# HDMI.net
KiCad netlist of a schematic drawn in Altium Designer
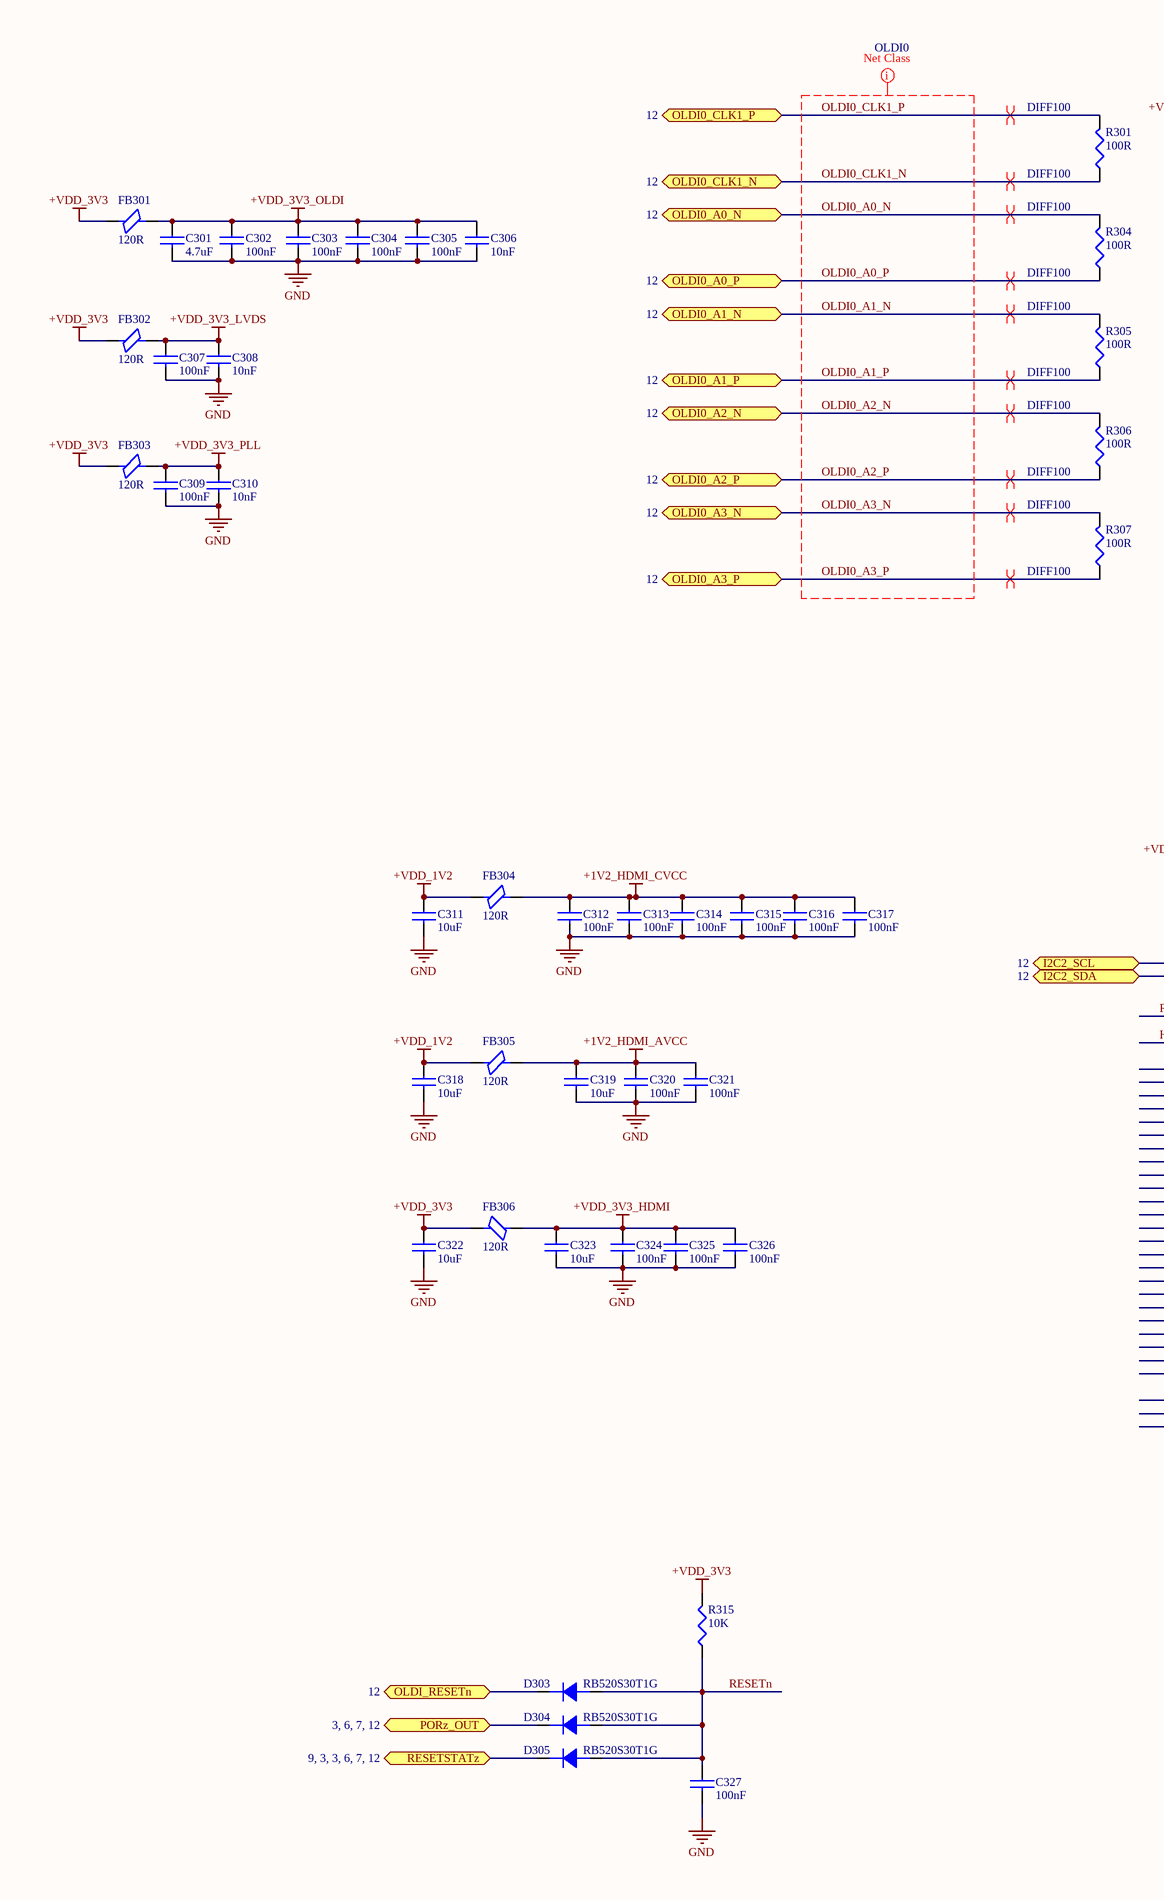
[diagram p0: HDMI.SchDoc, left]
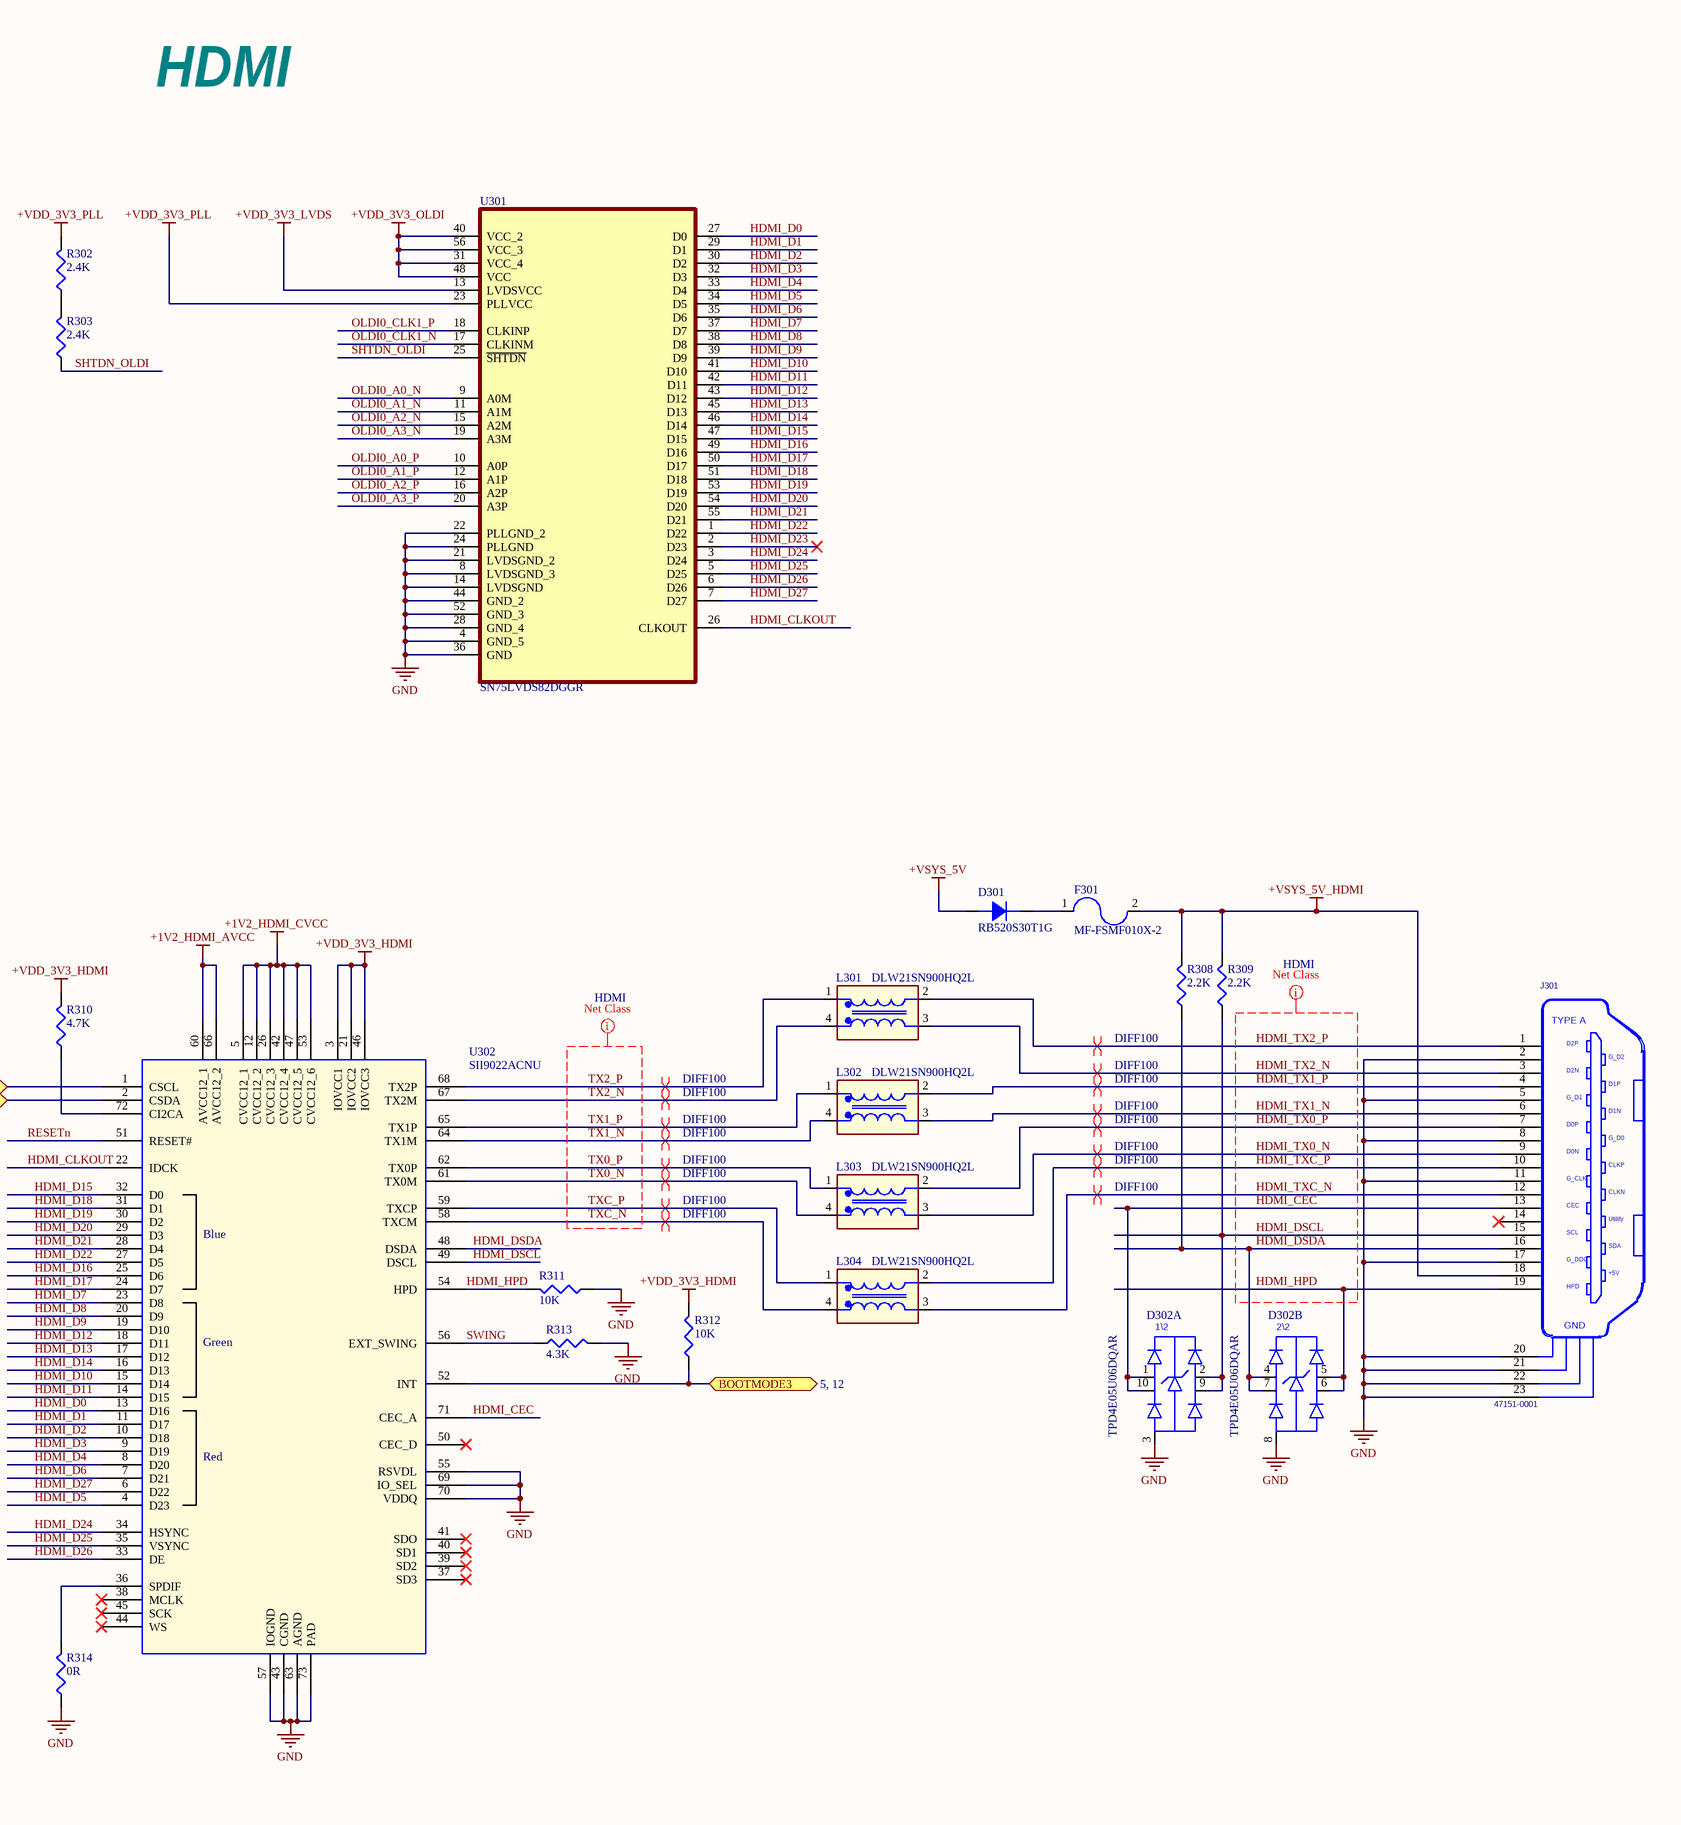
[diagram p1: HDMI.SchDoc, right]

(export (version "E")
  (design (tool "Eeschema 10.0.6"))
  (components
    (comp (ref "C301")
      (value "4.7uF")
      (footprint "C0402")
      (description "Multilayer Ceramic Capacitor, 4.7 uF, 6.3V, ± 10%, X5R, 0402 [1005 Metric]")
      (fields
        (field (name "MANUFACTURER") "Yageo")
        (field (name "MANUFACTURER PART NUMBER") "CC0402MRX5R5BB475")
      )
      (libsource (lib "Schlib SOM AM625") (part "CC0402MRX5R5BB475"))
    )
    (comp (ref "C302")
      (value "100nF")
      (footprint "C0603")
      (description "Multilayer Ceramic Capacitor, 0.1 uF, 25 V, ± 10%, X7R, 0603 [1608 Metric]")
      (fields
        (field (name "MANUFACTURER") "TDK")
        (field (name "MANUFACTURER PART NUMBER") "C1608X7R1E104K080AA")
      )
      (libsource (lib "Schlib SOM AM625") (part "C1608X7R1E104K080AA"))
    )
    (comp (ref "C303")
      (value "100nF")
      (footprint "C0603")
      (description "Multilayer Ceramic Capacitor, 0.1 uF, 25 V, ± 10%, X7R, 0603 [1608 Metric]")
      (fields
        (field (name "MANUFACTURER") "TDK")
        (field (name "MANUFACTURER PART NUMBER") "C1608X7R1E104K080AA")
      )
      (libsource (lib "Schlib SOM AM625") (part "C1608X7R1E104K080AA"))
    )
    (comp (ref "C304")
      (value "100nF")
      (footprint "C0603")
      (description "Multilayer Ceramic Capacitor, 0.1 uF, 25 V, ± 10%, X7R, 0603 [1608 Metric]")
      (fields
        (field (name "MANUFACTURER") "TDK")
        (field (name "MANUFACTURER PART NUMBER") "C1608X7R1E104K080AA")
      )
      (libsource (lib "Schlib SOM AM625") (part "C1608X7R1E104K080AA"))
    )
    (comp (ref "C305")
      (value "100nF")
      (footprint "C0603")
      (description "Multilayer Ceramic Capacitor, 0.1 uF, 25 V, ± 10%, X7R, 0603 [1608 Metric]")
      (fields
        (field (name "MANUFACTURER") "TDK")
        (field (name "MANUFACTURER PART NUMBER") "C1608X7R1E104K080AA")
      )
      (libsource (lib "Schlib SOM AM625") (part "C1608X7R1E104K080AA"))
    )
    (comp (ref "C306")
      (value "10nF")
      (footprint "C0402")
      (description "ESD SMD Comm X7R 0402 (1005Metric) ceramic capacitor 0.039Lx0.020W 1.00mmx0.50mm X7R ±10% 10000pF")
      (fields
        (field (name "MANUFACTURER") "KEMET")
        (field (name "MANUFACTURER PART NUMBER") "C0402C103K4REC7411")
      )
      (libsource (lib "Schlib SOM AM625") (part "C0402C103K4REC7411"))
    )
    (comp (ref "C307")
      (value "100nF")
      (footprint "C0603")
      (description "Multilayer Ceramic Capacitor, 0.1 uF, 25 V, ± 10%, X7R, 0603 [1608 Metric]")
      (fields
        (field (name "MANUFACTURER") "TDK")
        (field (name "MANUFACTURER PART NUMBER") "C1608X7R1E104K080AA")
      )
      (libsource (lib "Schlib SOM AM625") (part "C1608X7R1E104K080AA"))
    )
    (comp (ref "C308")
      (value "10nF")
      (footprint "C0402")
      (description "ESD SMD Comm X7R 0402 (1005Metric) ceramic capacitor 0.039Lx0.020W 1.00mmx0.50mm X7R ±10% 10000pF")
      (fields
        (field (name "MANUFACTURER") "KEMET")
        (field (name "MANUFACTURER PART NUMBER") "C0402C103K4REC7411")
      )
      (libsource (lib "Schlib SOM AM625") (part "C0402C103K4REC7411"))
    )
    (comp (ref "C309")
      (value "100nF")
      (footprint "C0603")
      (description "Multilayer Ceramic Capacitor, 0.1 uF, 25 V, ± 10%, X7R, 0603 [1608 Metric]")
      (fields
        (field (name "MANUFACTURER") "TDK")
        (field (name "MANUFACTURER PART NUMBER") "C1608X7R1E104K080AA")
      )
      (libsource (lib "Schlib SOM AM625") (part "C1608X7R1E104K080AA"))
    )
    (comp (ref "C310")
      (value "10nF")
      (footprint "C0402")
      (description "ESD SMD Comm X7R 0402 (1005Metric) ceramic capacitor 0.039Lx0.020W 1.00mmx0.50mm X7R ±10% 10000pF")
      (fields
        (field (name "MANUFACTURER") "KEMET")
        (field (name "MANUFACTURER PART NUMBER") "C0402C103K4REC7411")
      )
      (libsource (lib "Schlib SOM AM625") (part "C0402C103K4REC7411"))
    )
    (comp (ref "C311")
      (value "10uF")
      (footprint "C0603")
      (description "Multilayer Ceramic Capacitor, 10 uF, 10 V, ± 10%, X5R, 0603 [1608 Metric]")
      (fields
        (field (name "MANUFACTURER") "TDK")
        (field (name "MANUFACTURER PART NUMBER") "C1608X5R1A106K080AC")
      )
      (libsource (lib "Schlib SOM AM625") (part "C1608X5R1A106K080AC"))
    )
    (comp (ref "C312")
      (value "100nF")
      (footprint "C0201")
      (description "Multilayer Ceramic Capacitor, 0.1 uF, 16 V, ± 10%, X5R, 0201 [0603 Metric]")
      (fields
        (field (name "MANUFACTURER") "Yageo")
        (field (name "MANUFACTURER PART NUMBER") "CC0201KRX5R6BB104")
      )
      (libsource (lib "Schlib SOM AM625") (part "CC0201KRX5R6BB104"))
    )
    (comp (ref "C313")
      (value "100nF")
      (footprint "C0201")
      (description "Multilayer Ceramic Capacitor, 0.1 uF, 16 V, ± 10%, X5R, 0201 [0603 Metric]")
      (fields
        (field (name "MANUFACTURER") "Yageo")
        (field (name "MANUFACTURER PART NUMBER") "CC0201KRX5R6BB104")
      )
      (libsource (lib "Schlib SOM AM625") (part "CC0201KRX5R6BB104"))
    )
    (comp (ref "C314")
      (value "100nF")
      (footprint "C0201")
      (description "Multilayer Ceramic Capacitor, 0.1 uF, 16 V, ± 10%, X5R, 0201 [0603 Metric]")
      (fields
        (field (name "MANUFACTURER") "Yageo")
        (field (name "MANUFACTURER PART NUMBER") "CC0201KRX5R6BB104")
      )
      (libsource (lib "Schlib SOM AM625") (part "CC0201KRX5R6BB104"))
    )
    (comp (ref "C315")
      (value "100nF")
      (footprint "C0201")
      (description "Multilayer Ceramic Capacitor, 0.1 uF, 16 V, ± 10%, X5R, 0201 [0603 Metric]")
      (fields
        (field (name "MANUFACTURER") "Yageo")
        (field (name "MANUFACTURER PART NUMBER") "CC0201KRX5R6BB104")
      )
      (libsource (lib "Schlib SOM AM625") (part "CC0201KRX5R6BB104"))
    )
    (comp (ref "C316")
      (value "100nF")
      (footprint "C0201")
      (description "Multilayer Ceramic Capacitor, 0.1 uF, 16 V, ± 10%, X5R, 0201 [0603 Metric]")
      (fields
        (field (name "MANUFACTURER") "Yageo")
        (field (name "MANUFACTURER PART NUMBER") "CC0201KRX5R6BB104")
      )
      (libsource (lib "Schlib SOM AM625") (part "CC0201KRX5R6BB104"))
    )
    (comp (ref "C317")
      (value "100nF")
      (footprint "C0201")
      (description "Multilayer Ceramic Capacitor, 0.1 uF, 16 V, ± 10%, X5R, 0201 [0603 Metric]")
      (fields
        (field (name "MANUFACTURER") "Yageo")
        (field (name "MANUFACTURER PART NUMBER") "CC0201KRX5R6BB104")
      )
      (libsource (lib "Schlib SOM AM625") (part "CC0201KRX5R6BB104"))
    )
    (comp (ref "C318")
      (value "10uF")
      (footprint "C0603")
      (description "Multilayer Ceramic Capacitor, 10 uF, 10 V, ± 10%, X5R, 0603 [1608 Metric]")
      (fields
        (field (name "MANUFACTURER") "TDK")
        (field (name "MANUFACTURER PART NUMBER") "C1608X5R1A106K080AC")
      )
      (libsource (lib "Schlib SOM AM625") (part "C1608X5R1A106K080AC"))
    )
    (comp (ref "C319")
      (value "10uF")
      (footprint "C0603")
      (description "Multilayer Ceramic Capacitor, 10 uF, 10 V, ± 10%, X5R, 0603 [1608 Metric]")
      (fields
        (field (name "MANUFACTURER") "TDK")
        (field (name "MANUFACTURER PART NUMBER") "C1608X5R1A106K080AC")
      )
      (libsource (lib "Schlib SOM AM625") (part "C1608X5R1A106K080AC"))
    )
    (comp (ref "C320")
      (value "100nF")
      (footprint "C0201")
      (description "Multilayer Ceramic Capacitor, 0.1 uF, 16 V, ± 10%, X5R, 0201 [0603 Metric]")
      (fields
        (field (name "MANUFACTURER") "Yageo")
        (field (name "MANUFACTURER PART NUMBER") "CC0201KRX5R6BB104")
      )
      (libsource (lib "Schlib SOM AM625") (part "CC0201KRX5R6BB104"))
    )
    (comp (ref "C321")
      (value "100nF")
      (footprint "C0201")
      (description "Multilayer Ceramic Capacitor, 0.1 uF, 16 V, ± 10%, X5R, 0201 [0603 Metric]")
      (fields
        (field (name "MANUFACTURER") "Yageo")
        (field (name "MANUFACTURER PART NUMBER") "CC0201KRX5R6BB104")
      )
      (libsource (lib "Schlib SOM AM625") (part "CC0201KRX5R6BB104"))
    )
    (comp (ref "C322")
      (value "10uF")
      (footprint "C0603")
      (description "Multilayer Ceramic Capacitor, 10 uF, 10 V, ± 10%, X5R, 0603 [1608 Metric]")
      (fields
        (field (name "MANUFACTURER") "TDK")
        (field (name "MANUFACTURER PART NUMBER") "C1608X5R1A106K080AC")
      )
      (libsource (lib "Schlib SOM AM625") (part "C1608X5R1A106K080AC"))
    )
    (comp (ref "C323")
      (value "10uF")
      (footprint "C0603")
      (description "Multilayer Ceramic Capacitor, 10 uF, 10 V, ± 10%, X5R, 0603 [1608 Metric]")
      (fields
        (field (name "MANUFACTURER") "TDK")
        (field (name "MANUFACTURER PART NUMBER") "C1608X5R1A106K080AC")
      )
      (libsource (lib "Schlib SOM AM625") (part "C1608X5R1A106K080AC"))
    )
    (comp (ref "C324")
      (value "100nF")
      (footprint "C0201")
      (description "Multilayer Ceramic Capacitor, 0.1 uF, 16 V, ± 10%, X5R, 0201 [0603 Metric]")
      (fields
        (field (name "MANUFACTURER") "Yageo")
        (field (name "MANUFACTURER PART NUMBER") "CC0201KRX5R6BB104")
      )
      (libsource (lib "Schlib SOM AM625") (part "CC0201KRX5R6BB104"))
    )
    (comp (ref "C325")
      (value "100nF")
      (footprint "C0201")
      (description "Multilayer Ceramic Capacitor, 0.1 uF, 16 V, ± 10%, X5R, 0201 [0603 Metric]")
      (fields
        (field (name "MANUFACTURER") "Yageo")
        (field (name "MANUFACTURER PART NUMBER") "CC0201KRX5R6BB104")
      )
      (libsource (lib "Schlib SOM AM625") (part "CC0201KRX5R6BB104"))
    )
    (comp (ref "C326")
      (value "100nF")
      (footprint "C0201")
      (description "Multilayer Ceramic Capacitor, 0.1 uF, 16 V, ± 10%, X5R, 0201 [0603 Metric]")
      (fields
        (field (name "MANUFACTURER") "Yageo")
        (field (name "MANUFACTURER PART NUMBER") "CC0201KRX5R6BB104")
      )
      (libsource (lib "Schlib SOM AM625") (part "CC0201KRX5R6BB104"))
    )
    (comp (ref "C327")
      (value "100nF")
      (footprint "C0201")
      (description "Multilayer Ceramic Capacitor, 0.1 uF, 16 V, ± 10%, X5R, 0201 [0603 Metric]")
      (fields
        (field (name "MANUFACTURER") "Yageo")
        (field (name "MANUFACTURER PART NUMBER") "CC0201KRX5R6BB104")
      )
      (libsource (lib "Schlib SOM AM625") (part "CC0201KRX5R6BB104"))
    )
    (comp (ref "D301")
      (value "RB520S30T1G")
      (footprint "sod_523")
      (description "Diode Schottky 30V 0.2A 2-Pin SOD-523 T/R - Product that comes on tape, but is not reeled")
      (fields (field (name "MANUFACTURER") "ON Semiconductor"))
      (libsource (lib "Schlib SOM AM625") (part "RB520S30T1G"))
    )
    (comp (ref "D302")
      (value "TPD4E05U06DQAR")
      (footprint "10-USON")
      (description "Quad 0.5-pF, 5.5-V, ±12-kV ESD protection diode for USB, HDMI & High Speed Interfaces")
      (fields (field (name "MANUFACTURER") "Texas Instruments"))
      (libsource (lib "Schlib SOM AM625") (part "TPD4E05U06DQAR"))
    )
    (comp (ref "D303")
      (value "RB520S30T1G")
      (footprint "sod_523")
      (description "Diode Schottky 30V 0.2A 2-Pin SOD-523 T/R - Product that comes on tape, but is not reeled")
      (fields (field (name "MANUFACTURER") "ON Semiconductor"))
      (libsource (lib "Schlib SOM AM625") (part "RB520S30T1G"))
    )
    (comp (ref "D304")
      (value "RB520S30T1G")
      (footprint "sod_523")
      (description "Diode Schottky 30V 0.2A 2-Pin SOD-523 T/R - Product that comes on tape, but is not reeled")
      (fields (field (name "MANUFACTURER") "ON Semiconductor"))
      (libsource (lib "Schlib SOM AM625") (part "RB520S30T1G"))
    )
    (comp (ref "D305")
      (value "RB520S30T1G")
      (footprint "sod_523")
      (description "Diode Schottky 30V 0.2A 2-Pin SOD-523 T/R - Product that comes on tape, but is not reeled")
      (fields (field (name "MANUFACTURER") "ON Semiconductor"))
      (libsource (lib "Schlib SOM AM625") (part "RB520S30T1G"))
    )
    (comp (ref "F301")
      (value "MF-FSMF010X-2")
      (footprint "f0603")
      (fields (field (name "MANUFACTURER") "Bourns"))
      (libsource (lib "Schlib SOM AM625") (part "MF-FSMF010X-2"))
    )
    (comp (ref "FB301")
      (value "120R")
      (footprint "FB0402")
      (description "Ferrite Beads Multi-Layer 120Ohm 25% 100MHz 1.3A 0.09Ohm DCR 0402 Automotive T/R")
      (fields
        (field (name "MANUFACTURER") "Murata")
        (field (name "MANUFACTURER PART NUMBER") "BLM15PD121SZ1D")
      )
      (libsource (lib "Schlib SOM AM625") (part "BLM15PD121SZ1D"))
    )
    (comp (ref "FB302")
      (value "120R")
      (footprint "FB0402")
      (description "Ferrite Beads Multi-Layer 120Ohm 25% 100MHz 1.3A 0.09Ohm DCR 0402 Automotive T/R")
      (fields
        (field (name "MANUFACTURER") "Murata")
        (field (name "MANUFACTURER PART NUMBER") "BLM15PD121SZ1D")
      )
      (libsource (lib "Schlib SOM AM625") (part "BLM15PD121SZ1D"))
    )
    (comp (ref "FB303")
      (value "120R")
      (footprint "FB0402")
      (description "Ferrite Beads Multi-Layer 120Ohm 25% 100MHz 1.3A 0.09Ohm DCR 0402 Automotive T/R")
      (fields
        (field (name "MANUFACTURER") "Murata")
        (field (name "MANUFACTURER PART NUMBER") "BLM15PD121SZ1D")
      )
      (libsource (lib "Schlib SOM AM625") (part "BLM15PD121SZ1D"))
    )
    (comp (ref "FB304")
      (value "120R")
      (footprint "FB0402")
      (description "Ferrite Beads Multi-Layer 120Ohm 25% 100MHz 1.3A 0.09Ohm DCR 0402 Automotive T/R")
      (fields
        (field (name "MANUFACTURER") "Murata")
        (field (name "MANUFACTURER PART NUMBER") "BLM15PD121SZ1D")
      )
      (libsource (lib "Schlib SOM AM625") (part "BLM15PD121SZ1D"))
    )
    (comp (ref "FB305")
      (value "120R")
      (footprint "FB0402")
      (description "Ferrite Beads Multi-Layer 120Ohm 25% 100MHz 1.3A 0.09Ohm DCR 0402 Automotive T/R")
      (fields
        (field (name "MANUFACTURER") "Murata")
        (field (name "MANUFACTURER PART NUMBER") "BLM15PD121SZ1D")
      )
      (libsource (lib "Schlib SOM AM625") (part "BLM15PD121SZ1D"))
    )
    (comp (ref "FB306")
      (value "120R")
      (footprint "FB0402")
      (description "Ferrite Beads Multi-Layer 120Ohm 25% 100MHz 1.3A 0.09Ohm DCR 0402 Automotive T/R")
      (fields
        (field (name "MANUFACTURER") "Murata")
        (field (name "MANUFACTURER PART NUMBER") "BLM15PD121SZ1D")
      )
      (libsource (lib "Schlib SOM AM625") (part "BLM15PD121SZ1D"))
    )
    (comp (ref "J301")
      (value "47151-0001")
      (footprint "HDMI")
      (description "CONN RCPT 19POS HDMI RT ANG SMD")
      (fields (field (name "MANUFACTURER") "Molex Connector Corporation"))
      (libsource (lib "Schlib SOM AM625") (part "47151-0001"))
    )
    (comp (ref "L301")
      (value "DLW21SN900HQ2L")
      (footprint "IND_DLW21S_0805_MUR")
      (description "Ind Common Mode Choke Wirewound 90Ohm 25% 100MHz 280mA 0805 Embossed T/R")
      (fields (field (name "MANUFACTURER") "Murata") (field (name "TOLERANCE") "25%"))
      (libsource (lib "Schlib SOM AM625") (part "DLW21SN900HQ2L"))
    )
    (comp (ref "L302")
      (value "DLW21SN900HQ2L")
      (footprint "IND_DLW21S_0805_MUR")
      (description "Ind Common Mode Choke Wirewound 90Ohm 25% 100MHz 280mA 0805 Embossed T/R")
      (fields (field (name "MANUFACTURER") "Murata") (field (name "TOLERANCE") "25%"))
      (libsource (lib "Schlib SOM AM625") (part "DLW21SN900HQ2L"))
    )
    (comp (ref "L303")
      (value "DLW21SN900HQ2L")
      (footprint "IND_DLW21S_0805_MUR")
      (description "Ind Common Mode Choke Wirewound 90Ohm 25% 100MHz 280mA 0805 Embossed T/R")
      (fields (field (name "MANUFACTURER") "Murata") (field (name "TOLERANCE") "25%"))
      (libsource (lib "Schlib SOM AM625") (part "DLW21SN900HQ2L"))
    )
    (comp (ref "L304")
      (value "DLW21SN900HQ2L")
      (footprint "IND_DLW21S_0805_MUR")
      (description "Ind Common Mode Choke Wirewound 90Ohm 25% 100MHz 280mA 0805 Embossed T/R")
      (fields (field (name "MANUFACTURER") "Murata") (field (name "TOLERANCE") "25%"))
      (libsource (lib "Schlib SOM AM625") (part "DLW21SN900HQ2L"))
    )
    (comp (ref "R301")
      (value "100R")
      (footprint "R0402")
      (description "SMD Chip Resistor, 100 Ohm, ± 1%, 63 mW, 0402 [1005 Metric], Thick Film, General Purpose")
      (fields
        (field (name "MANUFACTURER") "Yageo")
        (field (name "MANUFACTURER PART NUMBER") "RC0402FR-07100RL")
      )
      (libsource (lib "Schlib SOM AM625") (part "RC0402FR-07100RL"))
    )
    (comp (ref "R302")
      (value "2.4K")
      (footprint "R0402")
      (description "Res Thick Film 0402 2.4K Ohm 5% 1/16W ±100ppm/°C Molded SMD Paper T/R")
      (fields
        (field (name "MANUFACTURER") "Yageo")
        (field (name "MANUFACTURER PART NUMBER") "RC0402JR-072K4L")
      )
      (libsource (lib "Schlib SOM AM625") (part "RC0402JR-072K4L"))
    )
    (comp (ref "R303")
      (value "2.4K")
      (footprint "R0402")
      (description "Res Thick Film 0402 2.4K Ohm 5% 1/16W ±100ppm/°C Molded SMD Paper T/R")
      (fields
        (field (name "MANUFACTURER") "Yageo")
        (field (name "MANUFACTURER PART NUMBER") "RC0402JR-072K4L")
      )
      (libsource (lib "Schlib SOM AM625") (part "RC0402JR-072K4L"))
    )
    (comp (ref "R304")
      (value "100R")
      (footprint "R0402")
      (description "SMD Chip Resistor, 100 Ohm, ± 1%, 63 mW, 0402 [1005 Metric], Thick Film, General Purpose")
      (fields
        (field (name "MANUFACTURER") "Yageo")
        (field (name "MANUFACTURER PART NUMBER") "RC0402FR-07100RL")
      )
      (libsource (lib "Schlib SOM AM625") (part "RC0402FR-07100RL"))
    )
    (comp (ref "R305")
      (value "100R")
      (footprint "R0402")
      (description "SMD Chip Resistor, 100 Ohm, ± 1%, 63 mW, 0402 [1005 Metric], Thick Film, General Purpose")
      (fields
        (field (name "MANUFACTURER") "Yageo")
        (field (name "MANUFACTURER PART NUMBER") "RC0402FR-07100RL")
      )
      (libsource (lib "Schlib SOM AM625") (part "RC0402FR-07100RL"))
    )
    (comp (ref "R306")
      (value "100R")
      (footprint "R0402")
      (description "SMD Chip Resistor, 100 Ohm, ± 1%, 63 mW, 0402 [1005 Metric], Thick Film, General Purpose")
      (fields
        (field (name "MANUFACTURER") "Yageo")
        (field (name "MANUFACTURER PART NUMBER") "RC0402FR-07100RL")
      )
      (libsource (lib "Schlib SOM AM625") (part "RC0402FR-07100RL"))
    )
    (comp (ref "R307")
      (value "100R")
      (footprint "R0402")
      (description "SMD Chip Resistor, 100 Ohm, ± 1%, 63 mW, 0402 [1005 Metric], Thick Film, General Purpose")
      (fields
        (field (name "MANUFACTURER") "Yageo")
        (field (name "MANUFACTURER PART NUMBER") "RC0402FR-07100RL")
      )
      (libsource (lib "Schlib SOM AM625") (part "RC0402FR-07100RL"))
    )
    (comp (ref "R308")
      (value "2.2K")
      (footprint "R0201")
      (description "SMD Chip Resistor, 2.2 kOhm, ± 1%, 50 mW, 0201 [0603 Metric], Thick Film, General Purpose")
      (fields
        (field (name "MANUFACTURER") "Yageo")
        (field (name "MANUFACTURER PART NUMBER") "RC0201FR-072K2L")
      )
      (libsource (lib "Schlib SOM AM625") (part "RC0201FR-072K2L"))
    )
    (comp (ref "R309")
      (value "2.2K")
      (footprint "R0201")
      (description "SMD Chip Resistor, 2.2 kOhm, ± 1%, 50 mW, 0201 [0603 Metric], Thick Film, General Purpose")
      (fields
        (field (name "MANUFACTURER") "Yageo")
        (field (name "MANUFACTURER PART NUMBER") "RC0201FR-072K2L")
      )
      (libsource (lib "Schlib SOM AM625") (part "RC0201FR-072K2L"))
    )
    (comp (ref "R310")
      (value "4.7K")
      (footprint "R0402")
      (description "SMD Chip Resistor, 4.7 kOhm, ± 1%, 63 mW, 0402 [1005 Metric], Thick Film, General Purpose")
      (fields
        (field (name "MANUFACTURER") "Yageo")
        (field (name "MANUFACTURER PART NUMBER") "RC0402FR-074K7L")
      )
      (libsource (lib "Schlib SOM AM625") (part "RC0402FR-074K7L"))
    )
    (comp (ref "R311")
      (value "10K")
      (footprint "R0201")
      (description "Res Thick Film 0201 10K Ohm 5% 1/20W ±200ppm/°C Molded SMD SMD Paper T/R")
      (fields
        (field (name "MANUFACTURER") "Yageo")
        (field (name "MANUFACTURER PART NUMBER") "RC0201JR-0710KL")
      )
      (libsource (lib "Schlib SOM AM625") (part "RC0201JR-0710KL"))
    )
    (comp (ref "R312")
      (value "10K")
      (footprint "R0201")
      (description "Res Thick Film 0201 10K Ohm 5% 1/20W ±200ppm/°C Molded SMD SMD Paper T/R")
      (fields
        (field (name "MANUFACTURER") "Yageo")
        (field (name "MANUFACTURER PART NUMBER") "RC0201JR-0710KL")
      )
      (libsource (lib "Schlib SOM AM625") (part "RC0201JR-0710KL"))
    )
    (comp (ref "R313")
      (value "4.3K")
      (footprint "R0402")
      (description "SMD Chip Resistor, 4.3 kOhm, ± 1%, 63 mW, 0402 [1005 Metric], Thick Film, General Purpose")
      (fields
        (field (name "MANUFACTURER") "Yageo")
        (field (name "MANUFACTURER PART NUMBER") "RC0402FR-074K3L")
      )
      (libsource (lib "Schlib SOM AM625") (part "RC0402FR-074K3L"))
    )
    (comp (ref "R314")
      (value "0R")
      (footprint "R0201")
      (description "Zero Ohm Resistor, Jumper, 0201 [0603 Metric], Thick Film, 50 mW, 500 mA, Surface Mount")
      (fields
        (field (name "MANUFACTURER") "Yageo")
        (field (name "MANUFACTURER PART NUMBER") "RC0201JR-070RL")
      )
      (libsource (lib "Schlib SOM AM625") (part "RC0201JR-070RL"))
    )
    (comp (ref "R315")
      (value "10K")
      (footprint "R0402")
      (description "RES 10.0K OHM 1/16W 1% 0402 SMD")
      (fields
        (field (name "MANUFACTURER") "Yageo")
        (field (name "MANUFACTURER PART NUMBER") "RC0402FR-0710KL")
      )
      (libsource (lib "Schlib SOM AM625") (part "RC0402FR-0710KL"))
    )
    (comp (ref "U301")
      (value "SN75LVDS82DGGR")
      (footprint "SOP50P810X120-56N")
      (description "0/5 Receiver  LVDS 56-TSSOP")
      (fields (field (name "MANUFACTURER") "Texas Instruments"))
      (libsource (lib "Schlib SOM AM625") (part "SN75LVDS82DGGR"))
    )
    (comp (ref "U302")
      (value "SII9022ACNU")
      (footprint "QFN50P1000X1000X90-73N")
      (description "24-Bit RGB Input HDMI 1.4a Transmitter, 1080p@60Hz, no HDCP, 72-pin QFN")
      (fields (field (name "MANUFACTURER") "Lattice Semiconductor"))
      (libsource (lib "Schlib SOM AM625") (part "SII9022ACNU"))
    )
  )
  (nets
    (net (code "1") (name "+1V2_HDMI_AVCC") (class "Default")
      (node (ref "C319") (pin "1") (pinfunction "1_1") (pintype "passive"))
      (node (ref "C320") (pin "1") (pinfunction "1_1") (pintype "passive"))
      (node (ref "C321") (pin "1") (pinfunction "1_1") (pintype "passive"))
      (node (ref "FB305") (pin "2") (pinfunction "2_2") (pintype "passive"))
      (node (ref "U302") (pin "60") (pinfunction "AVCC12_1_60") (pintype "passive"))
      (node (ref "U302") (pin "66") (pinfunction "AVCC12_2_66") (pintype "passive"))
    )
    (net (code "2") (name "+1V2_HDMI_CVCC") (class "Default")
      (node (ref "C312") (pin "1") (pinfunction "1_1") (pintype "passive"))
      (node (ref "C313") (pin "1") (pinfunction "1_1") (pintype "passive"))
      (node (ref "C314") (pin "1") (pinfunction "1_1") (pintype "passive"))
      (node (ref "C315") (pin "1") (pinfunction "1_1") (pintype "passive"))
      (node (ref "C316") (pin "1") (pinfunction "1_1") (pintype "passive"))
      (node (ref "C317") (pin "1") (pinfunction "1_1") (pintype "passive"))
      (node (ref "FB304") (pin "2") (pinfunction "2_2") (pintype "passive"))
      (node (ref "U302") (pin "12") (pinfunction "CVCC12_2_12") (pintype "passive"))
      (node (ref "U302") (pin "26") (pinfunction "CVCC12_3_26") (pintype "passive"))
      (node (ref "U302") (pin "42") (pinfunction "CVCC12_4_42") (pintype "passive"))
      (node (ref "U302") (pin "47") (pinfunction "CVCC12_5_47") (pintype "passive"))
      (node (ref "U302") (pin "5") (pinfunction "CVCC12_1_5") (pintype "passive"))
      (node (ref "U302") (pin "53") (pinfunction "CVCC12_6_53") (pintype "passive"))
    )
    (net (code "3") (name "+VDD_1V2") (class "Default")
      (node (ref "C311") (pin "1") (pinfunction "1_1") (pintype "passive"))
      (node (ref "C318") (pin "1") (pinfunction "1_1") (pintype "passive"))
      (node (ref "FB304") (pin "1") (pinfunction "1_1") (pintype "passive"))
      (node (ref "FB305") (pin "1") (pinfunction "1_1") (pintype "passive"))
    )
    (net (code "4") (name "+VDD_3V3") (class "Default")
      (node (ref "C322") (pin "1") (pinfunction "1_1") (pintype "passive"))
      (node (ref "FB301") (pin "1") (pinfunction "1_1") (pintype "passive"))
      (node (ref "FB302") (pin "1") (pinfunction "1_1") (pintype "passive"))
      (node (ref "FB303") (pin "1") (pinfunction "1_1") (pintype "passive"))
      (node (ref "FB306") (pin "2") (pinfunction "2_2") (pintype "passive"))
      (node (ref "R315") (pin "2") (pinfunction "2_2") (pintype "passive"))
    )
    (net (code "5") (name "+VDD_3V3_HDMI") (class "Default")
      (node (ref "C323") (pin "1") (pinfunction "1_1") (pintype "passive"))
      (node (ref "C324") (pin "1") (pinfunction "1_1") (pintype "passive"))
      (node (ref "C325") (pin "1") (pinfunction "1_1") (pintype "passive"))
      (node (ref "C326") (pin "1") (pinfunction "1_1") (pintype "passive"))
      (node (ref "FB306") (pin "1") (pinfunction "1_1") (pintype "passive"))
      (node (ref "R310") (pin "2") (pinfunction "2_2") (pintype "passive"))
      (node (ref "R312") (pin "2") (pinfunction "2_2") (pintype "passive"))
      (node (ref "U302") (pin "21") (pinfunction "IOVCC2_21") (pintype "passive"))
      (node (ref "U302") (pin "3") (pinfunction "IOVCC1_3") (pintype "passive"))
      (node (ref "U302") (pin "46") (pinfunction "IOVCC3_46") (pintype "passive"))
    )
    (net (code "6") (name "+VDD_3V3_LVDS") (class "Default")
      (node (ref "C307") (pin "1") (pinfunction "1_1") (pintype "passive"))
      (node (ref "C308") (pin "1") (pinfunction "1_1") (pintype "passive"))
      (node (ref "FB302") (pin "2") (pinfunction "2_2") (pintype "passive"))
      (node (ref "U301") (pin "13") (pinfunction "LVDSVCC_13") (pintype "passive"))
    )
    (net (code "7") (name "+VDD_3V3_OLDI") (class "Default")
      (node (ref "C301") (pin "1") (pinfunction "1_1") (pintype "passive"))
      (node (ref "C302") (pin "1") (pinfunction "1_1") (pintype "passive"))
      (node (ref "C303") (pin "1") (pinfunction "1_1") (pintype "passive"))
      (node (ref "C304") (pin "1") (pinfunction "1_1") (pintype "passive"))
      (node (ref "C305") (pin "1") (pinfunction "1_1") (pintype "passive"))
      (node (ref "C306") (pin "1") (pinfunction "1_1") (pintype "passive"))
      (node (ref "FB301") (pin "2") (pinfunction "2_2") (pintype "passive"))
      (node (ref "U301") (pin "31") (pinfunction "VCC_4_31") (pintype "passive"))
      (node (ref "U301") (pin "40") (pinfunction "VCC_2_40") (pintype "passive"))
      (node (ref "U301") (pin "48") (pinfunction "VCC_48") (pintype "passive"))
      (node (ref "U301") (pin "56") (pinfunction "VCC_3_56") (pintype "passive"))
    )
    (net (code "8") (name "+VDD_3V3_PLL") (class "Default")
      (node (ref "C309") (pin "1") (pinfunction "1_1") (pintype "passive"))
      (node (ref "C310") (pin "1") (pinfunction "1_1") (pintype "passive"))
      (node (ref "FB303") (pin "2") (pinfunction "2_2") (pintype "passive"))
      (node (ref "R302") (pin "2") (pinfunction "2_2") (pintype "passive"))
      (node (ref "U301") (pin "23") (pinfunction "PLLVCC_23") (pintype "passive"))
    )
    (net (code "9") (name "+VSYS_5V") (class "Default")
      (node (ref "D301") (pin "1") (pinfunction "A_1") (pintype "passive"))
    )
    (net (code "10") (name "+VSYS_5V_HDMI") (class "Default")
      (node (ref "F301") (pin "2") (pinfunction "2_2") (pintype "passive"))
      (node (ref "J301") (pin "18") (pinfunction "+5V_18") (pintype "passive"))
      (node (ref "R308") (pin "2") (pinfunction "2_2") (pintype "passive"))
      (node (ref "R309") (pin "2") (pinfunction "2_2") (pintype "passive"))
    )
    (net (code "11") (name "/BOOTMODE3") (class "Default")
      (node (ref "R312") (pin "1") (pinfunction "1_1") (pintype "passive"))
      (node (ref "U302") (pin "52") (pinfunction "INT_52") (pintype "passive"))
    )
    (net (code "12") (name "/HDMI_CEC") (class "Default")
      (node (ref "D302") (pin "1") (pinfunction "1A_1") (pintype "passive"))
      (node (ref "D302") (pin "10") (pinfunction "1B_10") (pintype "passive"))
      (node (ref "J301") (pin "13") (pinfunction "CEC_13") (pintype "passive"))
      (node (ref "U302") (pin "71") (pinfunction "CEC_A_71") (pintype "passive"))
    )
    (net (code "13") (name "/HDMI_CLKOUT") (class "Default")
      (node (ref "U301") (pin "26") (pinfunction "CLKOUT_26") (pintype "passive"))
      (node (ref "U302") (pin "22") (pinfunction "IDCK_22") (pintype "passive"))
    )
    (net (code "14") (name "/HDMI_D0") (class "Default")
      (node (ref "U301") (pin "27") (pinfunction "D0_27") (pintype "passive"))
      (node (ref "U302") (pin "13") (pinfunction "D16_13") (pintype "passive"))
    )
    (net (code "15") (name "/HDMI_D1") (class "Default")
      (node (ref "U301") (pin "29") (pinfunction "D1_29") (pintype "passive"))
      (node (ref "U302") (pin "11") (pinfunction "D17_11") (pintype "passive"))
    )
    (net (code "16") (name "/HDMI_D2") (class "Default")
      (node (ref "U301") (pin "30") (pinfunction "D2_30") (pintype "passive"))
      (node (ref "U302") (pin "10") (pinfunction "D18_10") (pintype "passive"))
    )
    (net (code "17") (name "/HDMI_D3") (class "Default")
      (node (ref "U301") (pin "32") (pinfunction "D3_32") (pintype "passive"))
      (node (ref "U302") (pin "9") (pinfunction "D19_9") (pintype "passive"))
    )
    (net (code "18") (name "/HDMI_D4") (class "Default")
      (node (ref "U301") (pin "33") (pinfunction "D4_33") (pintype "passive"))
      (node (ref "U302") (pin "8") (pinfunction "D20_8") (pintype "passive"))
    )
    (net (code "19") (name "/HDMI_D5") (class "Default")
      (node (ref "U301") (pin "34") (pinfunction "D5_34") (pintype "passive"))
      (node (ref "U302") (pin "4") (pinfunction "D23_4") (pintype "passive"))
    )
    (net (code "20") (name "/HDMI_D6") (class "Default")
      (node (ref "U301") (pin "35") (pinfunction "D6_35") (pintype "passive"))
      (node (ref "U302") (pin "7") (pinfunction "D21_7") (pintype "passive"))
    )
    (net (code "21") (name "/HDMI_D7") (class "Default")
      (node (ref "U301") (pin "37") (pinfunction "D7_37") (pintype "passive"))
      (node (ref "U302") (pin "23") (pinfunction "D8_23") (pintype "passive"))
    )
    (net (code "22") (name "/HDMI_D8") (class "Default")
      (node (ref "U301") (pin "38") (pinfunction "D8_38") (pintype "passive"))
      (node (ref "U302") (pin "20") (pinfunction "D9_20") (pintype "passive"))
    )
    (net (code "23") (name "/HDMI_D9") (class "Default")
      (node (ref "U301") (pin "39") (pinfunction "D9_39") (pintype "passive"))
      (node (ref "U302") (pin "19") (pinfunction "D10_19") (pintype "passive"))
    )
    (net (code "24") (name "/HDMI_D10") (class "Default")
      (node (ref "U301") (pin "41") (pinfunction "D10_41") (pintype "passive"))
      (node (ref "U302") (pin "15") (pinfunction "D14_15") (pintype "passive"))
    )
    (net (code "25") (name "/HDMI_D11") (class "Default")
      (node (ref "U301") (pin "42") (pinfunction "D11_42") (pintype "passive"))
      (node (ref "U302") (pin "14") (pinfunction "D15_14") (pintype "passive"))
    )
    (net (code "26") (name "/HDMI_D12") (class "Default")
      (node (ref "U301") (pin "43") (pinfunction "D12_43") (pintype "passive"))
      (node (ref "U302") (pin "18") (pinfunction "D11_18") (pintype "passive"))
    )
    (net (code "27") (name "/HDMI_D13") (class "Default")
      (node (ref "U301") (pin "45") (pinfunction "D13_45") (pintype "passive"))
      (node (ref "U302") (pin "17") (pinfunction "D12_17") (pintype "passive"))
    )
    (net (code "28") (name "/HDMI_D14") (class "Default")
      (node (ref "U301") (pin "46") (pinfunction "D14_46") (pintype "passive"))
      (node (ref "U302") (pin "16") (pinfunction "D13_16") (pintype "passive"))
    )
    (net (code "29") (name "/HDMI_D15") (class "Default")
      (node (ref "U301") (pin "47") (pinfunction "D15_47") (pintype "passive"))
      (node (ref "U302") (pin "32") (pinfunction "D0_32") (pintype "passive"))
    )
    (net (code "30") (name "/HDMI_D16") (class "Default")
      (node (ref "U301") (pin "49") (pinfunction "D16_49") (pintype "passive"))
      (node (ref "U302") (pin "25") (pinfunction "D6_25") (pintype "passive"))
    )
    (net (code "31") (name "/HDMI_D17") (class "Default")
      (node (ref "U301") (pin "50") (pinfunction "D17_50") (pintype "passive"))
      (node (ref "U302") (pin "24") (pinfunction "D7_24") (pintype "passive"))
    )
    (net (code "32") (name "/HDMI_D18") (class "Default")
      (node (ref "U301") (pin "51") (pinfunction "D18_51") (pintype "passive"))
      (node (ref "U302") (pin "31") (pinfunction "D1_31") (pintype "passive"))
    )
    (net (code "33") (name "/HDMI_D19") (class "Default")
      (node (ref "U301") (pin "53") (pinfunction "D19_53") (pintype "passive"))
      (node (ref "U302") (pin "30") (pinfunction "D2_30") (pintype "passive"))
    )
    (net (code "34") (name "/HDMI_D20") (class "Default")
      (node (ref "U301") (pin "54") (pinfunction "D20_54") (pintype "passive"))
      (node (ref "U302") (pin "29") (pinfunction "D3_29") (pintype "passive"))
    )
    (net (code "35") (name "/HDMI_D21") (class "Default")
      (node (ref "U301") (pin "55") (pinfunction "D21_55") (pintype "passive"))
      (node (ref "U302") (pin "28") (pinfunction "D4_28") (pintype "passive"))
    )
    (net (code "36") (name "/HDMI_D22") (class "Default")
      (node (ref "U301") (pin "1") (pinfunction "D22_1") (pintype "passive"))
      (node (ref "U302") (pin "27") (pinfunction "D5_27") (pintype "passive"))
    )
    (net (code "37") (name "/HDMI_D23") (class "Default")
      (node (ref "U301") (pin "2") (pinfunction "D23_2") (pintype "passive+no_connect"))
    )
    (net (code "38") (name "/HDMI_D24") (class "Default")
      (node (ref "U301") (pin "3") (pinfunction "D24_3") (pintype "passive"))
      (node (ref "U302") (pin "34") (pinfunction "HSYNC_34") (pintype "passive"))
    )
    (net (code "39") (name "/HDMI_D25") (class "Default")
      (node (ref "U301") (pin "5") (pinfunction "D25_5") (pintype "passive"))
      (node (ref "U302") (pin "35") (pinfunction "VSYNC_35") (pintype "passive"))
    )
    (net (code "40") (name "/HDMI_D26") (class "Default")
      (node (ref "U301") (pin "6") (pinfunction "D26_6") (pintype "passive"))
      (node (ref "U302") (pin "33") (pinfunction "DE_33") (pintype "passive"))
    )
    (net (code "41") (name "/HDMI_D27") (class "Default")
      (node (ref "U301") (pin "7") (pinfunction "D27_7") (pintype "passive"))
      (node (ref "U302") (pin "6") (pinfunction "D22_6") (pintype "passive"))
    )
    (net (code "42") (name "/HDMI_DSCL") (class "Default")
      (node (ref "D302") (pin "2") (pinfunction "2A_2") (pintype "passive"))
      (node (ref "D302") (pin "9") (pinfunction "2B_9") (pintype "passive"))
      (node (ref "J301") (pin "15") (pinfunction "SCL_15") (pintype "passive"))
      (node (ref "R309") (pin "1") (pinfunction "1_1") (pintype "passive"))
      (node (ref "U302") (pin "49") (pinfunction "DSCL_49") (pintype "passive"))
    )
    (net (code "43") (name "/HDMI_DSDA") (class "Default")
      (node (ref "D302") (pin "4") (pinfunction "3A_4") (pintype "passive"))
      (node (ref "D302") (pin "7") (pinfunction "3B_7") (pintype "passive"))
      (node (ref "J301") (pin "16") (pinfunction "SDA_16") (pintype "passive"))
      (node (ref "R308") (pin "1") (pinfunction "1_1") (pintype "passive"))
      (node (ref "U302") (pin "48") (pinfunction "DSDA_48") (pintype "passive"))
    )
    (net (code "44") (name "/HDMI_HPD") (class "Default")
      (node (ref "D302") (pin "5") (pinfunction "4A_5") (pintype "passive"))
      (node (ref "D302") (pin "6") (pinfunction "4B_6") (pintype "passive"))
      (node (ref "J301") (pin "19") (pinfunction "HPD_19") (pintype "passive"))
      (node (ref "R311") (pin "2") (pinfunction "2_2") (pintype "passive"))
      (node (ref "U302") (pin "54") (pinfunction "HPD_54") (pintype "passive"))
    )
    (net (code "45") (name "/HDMI_TX0_N") (class "Default")
      (node (ref "J301") (pin "9") (pinfunction "D0-_9") (pintype "passive"))
      (node (ref "L303") (pin "3") (pinfunction "3_3") (pintype "passive"))
    )
    (net (code "46") (name "/HDMI_TX0_P") (class "Default")
      (node (ref "J301") (pin "7") (pinfunction "D0+_7") (pintype "passive"))
      (node (ref "L303") (pin "2") (pinfunction "2_2") (pintype "passive"))
    )
    (net (code "47") (name "/HDMI_TX1_N") (class "Default")
      (node (ref "J301") (pin "6") (pinfunction "D1-_6") (pintype "passive"))
      (node (ref "L302") (pin "3") (pinfunction "3_3") (pintype "passive"))
    )
    (net (code "48") (name "/HDMI_TX1_P") (class "Default")
      (node (ref "J301") (pin "4") (pinfunction "D1+_4") (pintype "passive"))
      (node (ref "L302") (pin "2") (pinfunction "2_2") (pintype "passive"))
    )
    (net (code "49") (name "/HDMI_TX2_N") (class "Default")
      (node (ref "J301") (pin "3") (pinfunction "D2-_3") (pintype "passive"))
      (node (ref "L301") (pin "3") (pinfunction "3_3") (pintype "passive"))
    )
    (net (code "50") (name "/HDMI_TX2_P") (class "Default")
      (node (ref "J301") (pin "1") (pinfunction "D2+_1") (pintype "passive"))
      (node (ref "L301") (pin "2") (pinfunction "2_2") (pintype "passive"))
    )
    (net (code "51") (name "/HDMI_TXC_N") (class "Default")
      (node (ref "J301") (pin "12") (pinfunction "CK-_12") (pintype "passive"))
      (node (ref "L304") (pin "3") (pinfunction "3_3") (pintype "passive"))
    )
    (net (code "52") (name "/HDMI_TXC_P") (class "Default")
      (node (ref "J301") (pin "10") (pinfunction "CK+_10") (pintype "passive"))
      (node (ref "L304") (pin "2") (pinfunction "2_2") (pintype "passive"))
    )
    (net (code "53") (name "/I2C2_SCL") (class "Default")
      (node (ref "U302") (pin "1") (pinfunction "CSCL_1") (pintype "passive"))
    )
    (net (code "54") (name "/I2C2_SDA") (class "Default")
      (node (ref "U302") (pin "2") (pinfunction "CSDA_2") (pintype "passive"))
    )
    (net (code "55") (name "/OLDI0_A0_N") (class "Default")
      (node (ref "R304") (pin "2") (pinfunction "2_2") (pintype "passive"))
      (node (ref "U301") (pin "9") (pinfunction "A0M_9") (pintype "passive"))
    )
    (net (code "56") (name "/OLDI0_A0_P") (class "Default")
      (node (ref "R304") (pin "1") (pinfunction "1_1") (pintype "passive"))
      (node (ref "U301") (pin "10") (pinfunction "A0P_10") (pintype "passive"))
    )
    (net (code "57") (name "/OLDI0_A1_N") (class "Default")
      (node (ref "R305") (pin "2") (pinfunction "2_2") (pintype "passive"))
      (node (ref "U301") (pin "11") (pinfunction "A1M_11") (pintype "passive"))
    )
    (net (code "58") (name "/OLDI0_A1_P") (class "Default")
      (node (ref "R305") (pin "1") (pinfunction "1_1") (pintype "passive"))
      (node (ref "U301") (pin "12") (pinfunction "A1P_12") (pintype "passive"))
    )
    (net (code "59") (name "/OLDI0_A2_N") (class "Default")
      (node (ref "R306") (pin "2") (pinfunction "2_2") (pintype "passive"))
      (node (ref "U301") (pin "15") (pinfunction "A2M_15") (pintype "passive"))
    )
    (net (code "60") (name "/OLDI0_A2_P") (class "Default")
      (node (ref "R306") (pin "1") (pinfunction "1_1") (pintype "passive"))
      (node (ref "U301") (pin "16") (pinfunction "A2P_16") (pintype "passive"))
    )
    (net (code "61") (name "/OLDI0_A3_N") (class "Default")
      (node (ref "R307") (pin "2") (pinfunction "2_2") (pintype "passive"))
      (node (ref "U301") (pin "19") (pinfunction "A3M_19") (pintype "passive"))
    )
    (net (code "62") (name "/OLDI0_A3_P") (class "Default")
      (node (ref "R307") (pin "1") (pinfunction "1_1") (pintype "passive"))
      (node (ref "U301") (pin "20") (pinfunction "A3P_20") (pintype "passive"))
    )
    (net (code "63") (name "/OLDI0_CLK1_N") (class "Default")
      (node (ref "R301") (pin "1") (pinfunction "1_1") (pintype "passive"))
      (node (ref "U301") (pin "17") (pinfunction "CLKINM_17") (pintype "passive"))
    )
    (net (code "64") (name "/OLDI0_CLK1_P") (class "Default")
      (node (ref "R301") (pin "2") (pinfunction "2_2") (pintype "passive"))
      (node (ref "U301") (pin "18") (pinfunction "CLKINP_18") (pintype "passive"))
    )
    (net (code "65") (name "/OLDI_RESETn") (class "Default")
      (node (ref "D303") (pin "2") (pinfunction "C_2") (pintype "passive"))
    )
    (net (code "66") (name "/PORz_OUT") (class "Default")
      (node (ref "D304") (pin "2") (pinfunction "C_2") (pintype "passive"))
    )
    (net (code "67") (name "/RESETSTATz") (class "Default")
      (node (ref "D305") (pin "2") (pinfunction "C_2") (pintype "passive"))
    )
    (net (code "68") (name "/RESETn") (class "Default")
      (node (ref "C327") (pin "1") (pinfunction "1_1") (pintype "passive"))
      (node (ref "D303") (pin "1") (pinfunction "A_1") (pintype "passive"))
      (node (ref "D304") (pin "1") (pinfunction "A_1") (pintype "passive"))
      (node (ref "D305") (pin "1") (pinfunction "A_1") (pintype "passive"))
      (node (ref "R315") (pin "1") (pinfunction "1_1") (pintype "passive"))
      (node (ref "U302") (pin "51") (pinfunction "RESET#_51") (pintype "passive"))
    )
    (net (code "69") (name "/SHTDN_OLDI") (class "Default")
      (node (ref "R303") (pin "1") (pinfunction "1_1") (pintype "passive"))
      (node (ref "U301") (pin "25") (pinfunction "~{SHTDN}_25") (pintype "passive"))
    )
    (net (code "70") (name "/SWING") (class "Default")
      (node (ref "R313") (pin "1") (pinfunction "1_1") (pintype "passive"))
      (node (ref "U302") (pin "56") (pinfunction "EXT_SWING_56") (pintype "passive"))
    )
    (net (code "71") (name "/TX0_N") (class "Default")
      (node (ref "L303") (pin "4") (pinfunction "4_4") (pintype "passive"))
      (node (ref "U302") (pin "61") (pinfunction "TX0M_61") (pintype "passive"))
    )
    (net (code "72") (name "/TX0_P") (class "Default")
      (node (ref "L303") (pin "1") (pinfunction "1_1") (pintype "passive"))
      (node (ref "U302") (pin "62") (pinfunction "TX0P_62") (pintype "passive"))
    )
    (net (code "73") (name "/TX1_N") (class "Default")
      (node (ref "L302") (pin "4") (pinfunction "4_4") (pintype "passive"))
      (node (ref "U302") (pin "64") (pinfunction "TX1M_64") (pintype "passive"))
    )
    (net (code "74") (name "/TX1_P") (class "Default")
      (node (ref "L302") (pin "1") (pinfunction "1_1") (pintype "passive"))
      (node (ref "U302") (pin "65") (pinfunction "TX1P_65") (pintype "passive"))
    )
    (net (code "75") (name "/TX2_N") (class "Default")
      (node (ref "L301") (pin "4") (pinfunction "4_4") (pintype "passive"))
      (node (ref "U302") (pin "67") (pinfunction "TX2M_67") (pintype "passive"))
    )
    (net (code "76") (name "/TX2_P") (class "Default")
      (node (ref "L301") (pin "1") (pinfunction "1_1") (pintype "passive"))
      (node (ref "U302") (pin "68") (pinfunction "TX2P_68") (pintype "passive"))
    )
    (net (code "77") (name "/TXC_N") (class "Default")
      (node (ref "L304") (pin "4") (pinfunction "4_4") (pintype "passive"))
      (node (ref "U302") (pin "58") (pinfunction "TXCM_58") (pintype "passive"))
    )
    (net (code "78") (name "/TXC_P") (class "Default")
      (node (ref "L304") (pin "1") (pinfunction "1_1") (pintype "passive"))
      (node (ref "U302") (pin "59") (pinfunction "TXCP_59") (pintype "passive"))
    )
    (net (code "79") (name "GND") (class "Default")
      (node (ref "C301") (pin "2") (pinfunction "2_2") (pintype "passive"))
      (node (ref "C302") (pin "2") (pinfunction "2_2") (pintype "passive"))
      (node (ref "C303") (pin "2") (pinfunction "2_2") (pintype "passive"))
      (node (ref "C304") (pin "2") (pinfunction "2_2") (pintype "passive"))
      (node (ref "C305") (pin "2") (pinfunction "2_2") (pintype "passive"))
      (node (ref "C306") (pin "2") (pinfunction "2_2") (pintype "passive"))
      (node (ref "C307") (pin "2") (pinfunction "2_2") (pintype "passive"))
      (node (ref "C308") (pin "2") (pinfunction "2_2") (pintype "passive"))
      (node (ref "C309") (pin "2") (pinfunction "2_2") (pintype "passive"))
      (node (ref "C310") (pin "2") (pinfunction "2_2") (pintype "passive"))
      (node (ref "C311") (pin "2") (pinfunction "2_2") (pintype "passive"))
      (node (ref "C312") (pin "2") (pinfunction "2_2") (pintype "passive"))
      (node (ref "C313") (pin "2") (pinfunction "2_2") (pintype "passive"))
      (node (ref "C314") (pin "2") (pinfunction "2_2") (pintype "passive"))
      (node (ref "C315") (pin "2") (pinfunction "2_2") (pintype "passive"))
      (node (ref "C316") (pin "2") (pinfunction "2_2") (pintype "passive"))
      (node (ref "C317") (pin "2") (pinfunction "2_2") (pintype "passive"))
      (node (ref "C318") (pin "2") (pinfunction "2_2") (pintype "passive"))
      (node (ref "C319") (pin "2") (pinfunction "2_2") (pintype "passive"))
      (node (ref "C320") (pin "2") (pinfunction "2_2") (pintype "passive"))
      (node (ref "C321") (pin "2") (pinfunction "2_2") (pintype "passive"))
      (node (ref "C322") (pin "2") (pinfunction "2_2") (pintype "passive"))
      (node (ref "C323") (pin "2") (pinfunction "2_2") (pintype "passive"))
      (node (ref "C324") (pin "2") (pinfunction "2_2") (pintype "passive"))
      (node (ref "C325") (pin "2") (pinfunction "2_2") (pintype "passive"))
      (node (ref "C326") (pin "2") (pinfunction "2_2") (pintype "passive"))
      (node (ref "C327") (pin "2") (pinfunction "2_2") (pintype "passive"))
      (node (ref "D302") (pin "3") (pinfunction "GND1_3") (pintype "passive"))
      (node (ref "D302") (pin "8") (pinfunction "GND1_8") (pintype "passive"))
      (node (ref "J301") (pin "11") (pinfunction "CKGND_11") (pintype "power_in"))
      (node (ref "J301") (pin "17") (pinfunction "DDCGND_17") (pintype "power_in"))
      (node (ref "J301") (pin "2") (pinfunction "D2GND_2") (pintype "power_in"))
      (node (ref "J301") (pin "20") (pinfunction "GND1_20") (pintype "passive"))
      (node (ref "J301") (pin "21") (pinfunction "GND2_21") (pintype "passive"))
      (node (ref "J301") (pin "22") (pinfunction "GND3_22") (pintype "passive"))
      (node (ref "J301") (pin "23") (pinfunction "GND4_23") (pintype "passive"))
      (node (ref "J301") (pin "5") (pinfunction "D1GND_5") (pintype "power_in"))
      (node (ref "J301") (pin "8") (pinfunction "D0GND_8") (pintype "power_in"))
      (node (ref "R311") (pin "1") (pinfunction "1_1") (pintype "passive"))
      (node (ref "R313") (pin "2") (pinfunction "2_2") (pintype "passive"))
      (node (ref "R314") (pin "1") (pinfunction "1_1") (pintype "passive"))
      (node (ref "U301") (pin "14") (pinfunction "LVDSGND_14") (pintype "passive"))
      (node (ref "U301") (pin "21") (pinfunction "LVDSGND_2_21") (pintype "passive"))
      (node (ref "U301") (pin "22") (pinfunction "PLLGND_2_22") (pintype "passive"))
      (node (ref "U301") (pin "24") (pinfunction "PLLGND_24") (pintype "passive"))
      (node (ref "U301") (pin "28") (pinfunction "GND_4_28") (pintype "passive"))
      (node (ref "U301") (pin "36") (pinfunction "GND_36") (pintype "passive"))
      (node (ref "U301") (pin "4") (pinfunction "GND_5_4") (pintype "passive"))
      (node (ref "U301") (pin "44") (pinfunction "GND_2_44") (pintype "passive"))
      (node (ref "U301") (pin "52") (pinfunction "GND_3_52") (pintype "passive"))
      (node (ref "U301") (pin "8") (pinfunction "LVDSGND_3_8") (pintype "passive"))
      (node (ref "U302") (pin "43") (pinfunction "CGND_43") (pintype "passive"))
      (node (ref "U302") (pin "55") (pinfunction "RSVDL_55") (pintype "passive"))
      (node (ref "U302") (pin "57") (pinfunction "IOGND_57") (pintype "passive"))
      (node (ref "U302") (pin "63") (pinfunction "AGND_63") (pintype "passive"))
      (node (ref "U302") (pin "69") (pinfunction "IO_SEL_69") (pintype "passive"))
      (node (ref "U302") (pin "70") (pinfunction "VDDQ_70") (pintype "passive"))
      (node (ref "U302") (pin "73") (pinfunction "PAD_73") (pintype "passive"))
    )
    (net (code "80") (name "Net-(D301-C)") (class "Default")
      (node (ref "D301") (pin "2") (pinfunction "C_2") (pintype "passive"))
      (node (ref "F301") (pin "1") (pinfunction "1_1") (pintype "passive"))
    )
    (net (code "81") (name "Net-(R302-Pad1)") (class "Default")
      (node (ref "R302") (pin "1") (pinfunction "1_1") (pintype "passive"))
      (node (ref "R303") (pin "2") (pinfunction "2_2") (pintype "passive"))
    )
    (net (code "82") (name "Net-(U302-CI2CA)") (class "Default")
      (node (ref "R310") (pin "1") (pinfunction "1_1") (pintype "passive"))
      (node (ref "U302") (pin "72") (pinfunction "CI2CA_72") (pintype "passive"))
    )
    (net (code "83") (name "Net-(U302-SPDIF)") (class "Default")
      (node (ref "R314") (pin "2") (pinfunction "2_2") (pintype "passive"))
      (node (ref "U302") (pin "36") (pinfunction "SPDIF_36") (pintype "passive"))
    )
    (net (code "84") (name "unconnected-(J301-Utility-Pad14)") (class "Default")
      (node (ref "J301") (pin "14") (pinfunction "Utility_14") (pintype "passive+no_connect"))
    )
    (net (code "85") (name "unconnected-(U302-CEC_D-Pad50)") (class "Default")
      (node (ref "U302") (pin "50") (pinfunction "CEC_D_50") (pintype "passive+no_connect"))
    )
    (net (code "86") (name "unconnected-(U302-MCLK-Pad38)") (class "Default")
      (node (ref "U302") (pin "38") (pinfunction "MCLK_38") (pintype "passive+no_connect"))
    )
    (net (code "87") (name "unconnected-(U302-SCK-Pad45)") (class "Default")
      (node (ref "U302") (pin "45") (pinfunction "SCK_45") (pintype "passive+no_connect"))
    )
    (net (code "88") (name "unconnected-(U302-SD1-Pad40)") (class "Default")
      (node (ref "U302") (pin "40") (pinfunction "SD1_40") (pintype "passive+no_connect"))
    )
    (net (code "89") (name "unconnected-(U302-SD2-Pad39)") (class "Default")
      (node (ref "U302") (pin "39") (pinfunction "SD2_39") (pintype "passive+no_connect"))
    )
    (net (code "90") (name "unconnected-(U302-SD3-Pad37)") (class "Default")
      (node (ref "U302") (pin "37") (pinfunction "SD3_37") (pintype "passive+no_connect"))
    )
    (net (code "91") (name "unconnected-(U302-SDO-Pad41)") (class "Default")
      (node (ref "U302") (pin "41") (pinfunction "SDO_41") (pintype "passive+no_connect"))
    )
    (net (code "92") (name "unconnected-(U302-WS-Pad44)") (class "Default")
      (node (ref "U302") (pin "44") (pinfunction "WS_44") (pintype "passive+no_connect"))
    )
  )
)
